# LED_Control.net
KiCad netlist of a schematic drawn in EAGLE
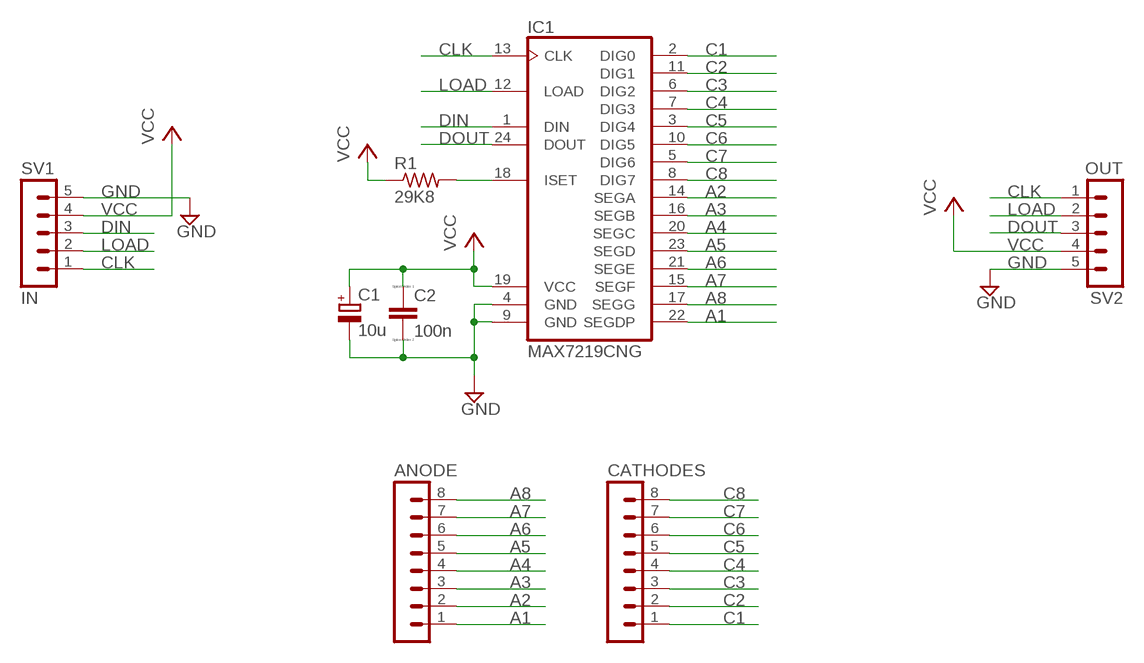
[diagram p0: schematic, sheet 1]

(export (version "E")
  (design (tool "Eeschema 10.0.6"))
  (components
    (comp (ref "ANODE")
      (value "MA08-1")
      (footprint "eagle-import:MA08-1")
      (libsource (lib "eagle-import") (part "MA08-1"))
    )
    (comp (ref "C1")
      (value "10u")
      (footprint "eagle-import:E2-5")
      (libsource (lib "eagle-import") (part "CPOL-EUE2-5"))
    )
    (comp (ref "C2")
      (value "100n")
      (footprint "eagle-import:C025-025X050")
      (libsource (lib "eagle-import") (part "C-EU025-025X050"))
    )
    (comp (ref "CATHODES")
      (value "MA08-1")
      (footprint "eagle-import:MA08-1")
      (libsource (lib "eagle-import") (part "MA08-1"))
    )
    (comp (ref "IC1")
      (value "MAX7219CNG")
      (footprint "eagle-import:DIL24-3")
      (libsource (lib "eagle-import") (part "MAX7219CNG"))
    )
    (comp (ref "R1")
      (value "29K8")
      (footprint "eagle-import:0204_7")
      (libsource (lib "eagle-import") (part "R-US_0204/7"))
    )
    (comp (ref "SV1")
      (value "IN")
      (footprint "eagle-import:MA05-1")
      (libsource (lib "eagle-import") (part "MA05-1"))
    )
    (comp (ref "SV2")
      (value "OUT")
      (footprint "eagle-import:MA05-1")
      (libsource (lib "eagle-import") (part "MA05-1"))
    )
  )
  (nets
    (net (code "1") (name "/A1") (class "Default")
      (node (ref "ANODE") (pin "1") (pinfunction "1_1") (pintype "passive"))
      (node (ref "IC1") (pin "22") (pinfunction "SEGDP_22") (pintype "output"))
    )
    (net (code "2") (name "/A2") (class "Default")
      (node (ref "ANODE") (pin "2") (pinfunction "2_2") (pintype "passive"))
      (node (ref "IC1") (pin "14") (pinfunction "SEGA_14") (pintype "output"))
    )
    (net (code "3") (name "/A3") (class "Default")
      (node (ref "ANODE") (pin "3") (pinfunction "3_3") (pintype "passive"))
      (node (ref "IC1") (pin "16") (pinfunction "SEGB_16") (pintype "output"))
    )
    (net (code "4") (name "/A4") (class "Default")
      (node (ref "ANODE") (pin "4") (pinfunction "4_4") (pintype "passive"))
      (node (ref "IC1") (pin "20") (pinfunction "SEGC_20") (pintype "output"))
    )
    (net (code "5") (name "/A5") (class "Default")
      (node (ref "ANODE") (pin "5") (pinfunction "5_5") (pintype "passive"))
      (node (ref "IC1") (pin "23") (pinfunction "SEGD_23") (pintype "output"))
    )
    (net (code "6") (name "/A6") (class "Default")
      (node (ref "ANODE") (pin "6") (pinfunction "6_6") (pintype "passive"))
      (node (ref "IC1") (pin "21") (pinfunction "SEGE_21") (pintype "output"))
    )
    (net (code "7") (name "/A7") (class "Default")
      (node (ref "ANODE") (pin "7") (pinfunction "7_7") (pintype "passive"))
      (node (ref "IC1") (pin "15") (pinfunction "SEGF_15") (pintype "output"))
    )
    (net (code "8") (name "/A8") (class "Default")
      (node (ref "ANODE") (pin "8") (pinfunction "8_8") (pintype "passive"))
      (node (ref "IC1") (pin "17") (pinfunction "SEGG_17") (pintype "output"))
    )
    (net (code "9") (name "/C1") (class "Default")
      (node (ref "CATHODES") (pin "1") (pinfunction "1_1") (pintype "passive"))
      (node (ref "IC1") (pin "2") (pinfunction "DIG0_2") (pintype "output"))
    )
    (net (code "10") (name "/C2") (class "Default")
      (node (ref "CATHODES") (pin "2") (pinfunction "2_2") (pintype "passive"))
      (node (ref "IC1") (pin "11") (pinfunction "DIG1_11") (pintype "output"))
    )
    (net (code "11") (name "/C3") (class "Default")
      (node (ref "CATHODES") (pin "3") (pinfunction "3_3") (pintype "passive"))
      (node (ref "IC1") (pin "6") (pinfunction "DIG2_6") (pintype "output"))
    )
    (net (code "12") (name "/C4") (class "Default")
      (node (ref "CATHODES") (pin "4") (pinfunction "4_4") (pintype "passive"))
      (node (ref "IC1") (pin "7") (pinfunction "DIG3_7") (pintype "output"))
    )
    (net (code "13") (name "/C5") (class "Default")
      (node (ref "CATHODES") (pin "5") (pinfunction "5_5") (pintype "passive"))
      (node (ref "IC1") (pin "3") (pinfunction "DIG4_3") (pintype "output"))
    )
    (net (code "14") (name "/C6") (class "Default")
      (node (ref "CATHODES") (pin "6") (pinfunction "6_6") (pintype "passive"))
      (node (ref "IC1") (pin "10") (pinfunction "DIG5_10") (pintype "output"))
    )
    (net (code "15") (name "/C7") (class "Default")
      (node (ref "CATHODES") (pin "7") (pinfunction "7_7") (pintype "passive"))
      (node (ref "IC1") (pin "5") (pinfunction "DIG6_5") (pintype "output"))
    )
    (net (code "16") (name "/C8") (class "Default")
      (node (ref "CATHODES") (pin "8") (pinfunction "8_8") (pintype "passive"))
      (node (ref "IC1") (pin "8") (pinfunction "DIG7_8") (pintype "output"))
    )
    (net (code "17") (name "/CLK") (class "Default")
      (node (ref "IC1") (pin "13") (pinfunction "CLK_13") (pintype "input"))
      (node (ref "SV1") (pin "1") (pinfunction "1_1") (pintype "passive"))
      (node (ref "SV2") (pin "1") (pinfunction "1_1") (pintype "passive"))
    )
    (net (code "18") (name "/DIN") (class "Default")
      (node (ref "IC1") (pin "1") (pinfunction "DIN_1") (pintype "input"))
      (node (ref "SV1") (pin "3") (pinfunction "3_3") (pintype "passive"))
    )
    (net (code "19") (name "/DOUT") (class "Default")
      (node (ref "IC1") (pin "24") (pinfunction "DOUT_24") (pintype "output"))
      (node (ref "SV2") (pin "3") (pinfunction "3_3") (pintype "passive"))
    )
    (net (code "20") (name "/LOAD") (class "Default")
      (node (ref "IC1") (pin "12") (pinfunction "LOAD_12") (pintype "input"))
      (node (ref "SV1") (pin "2") (pinfunction "2_2") (pintype "passive"))
      (node (ref "SV2") (pin "2") (pinfunction "2_2") (pintype "passive"))
    )
    (net (code "21") (name "GND") (class "Default")
      (node (ref "C1") (pin "-") (pinfunction "-_-") (pintype "passive"))
      (node (ref "C2") (pin "2") (pinfunction "2_2") (pintype "passive"))
      (node (ref "IC1") (pin "4") (pinfunction "GND_4") (pintype "power_in"))
      (node (ref "IC1") (pin "9") (pinfunction "GND_9") (pintype "power_in"))
      (node (ref "SV1") (pin "5") (pinfunction "5_5") (pintype "passive"))
      (node (ref "SV2") (pin "5") (pinfunction "5_5") (pintype "passive"))
    )
    (net (code "22") (name "Net-(IC1-ISET)") (class "Default")
      (node (ref "IC1") (pin "18") (pinfunction "ISET_18") (pintype "input"))
      (node (ref "R1") (pin "2") (pinfunction "2_2") (pintype "passive"))
    )
    (net (code "23") (name "VCC") (class "Default")
      (node (ref "C1") (pin "+") (pinfunction "+_+") (pintype "passive"))
      (node (ref "C2") (pin "1") (pinfunction "1_1") (pintype "passive"))
      (node (ref "IC1") (pin "19") (pinfunction "VCC_19") (pintype "power_in"))
      (node (ref "R1") (pin "1") (pinfunction "1_1") (pintype "passive"))
      (node (ref "SV1") (pin "4") (pinfunction "4_4") (pintype "passive"))
      (node (ref "SV2") (pin "4") (pinfunction "4_4") (pintype "passive"))
    )
  )
)
